# STM32_PAP_board.net
KiCad netlist of a schematic drawn in EAGLE
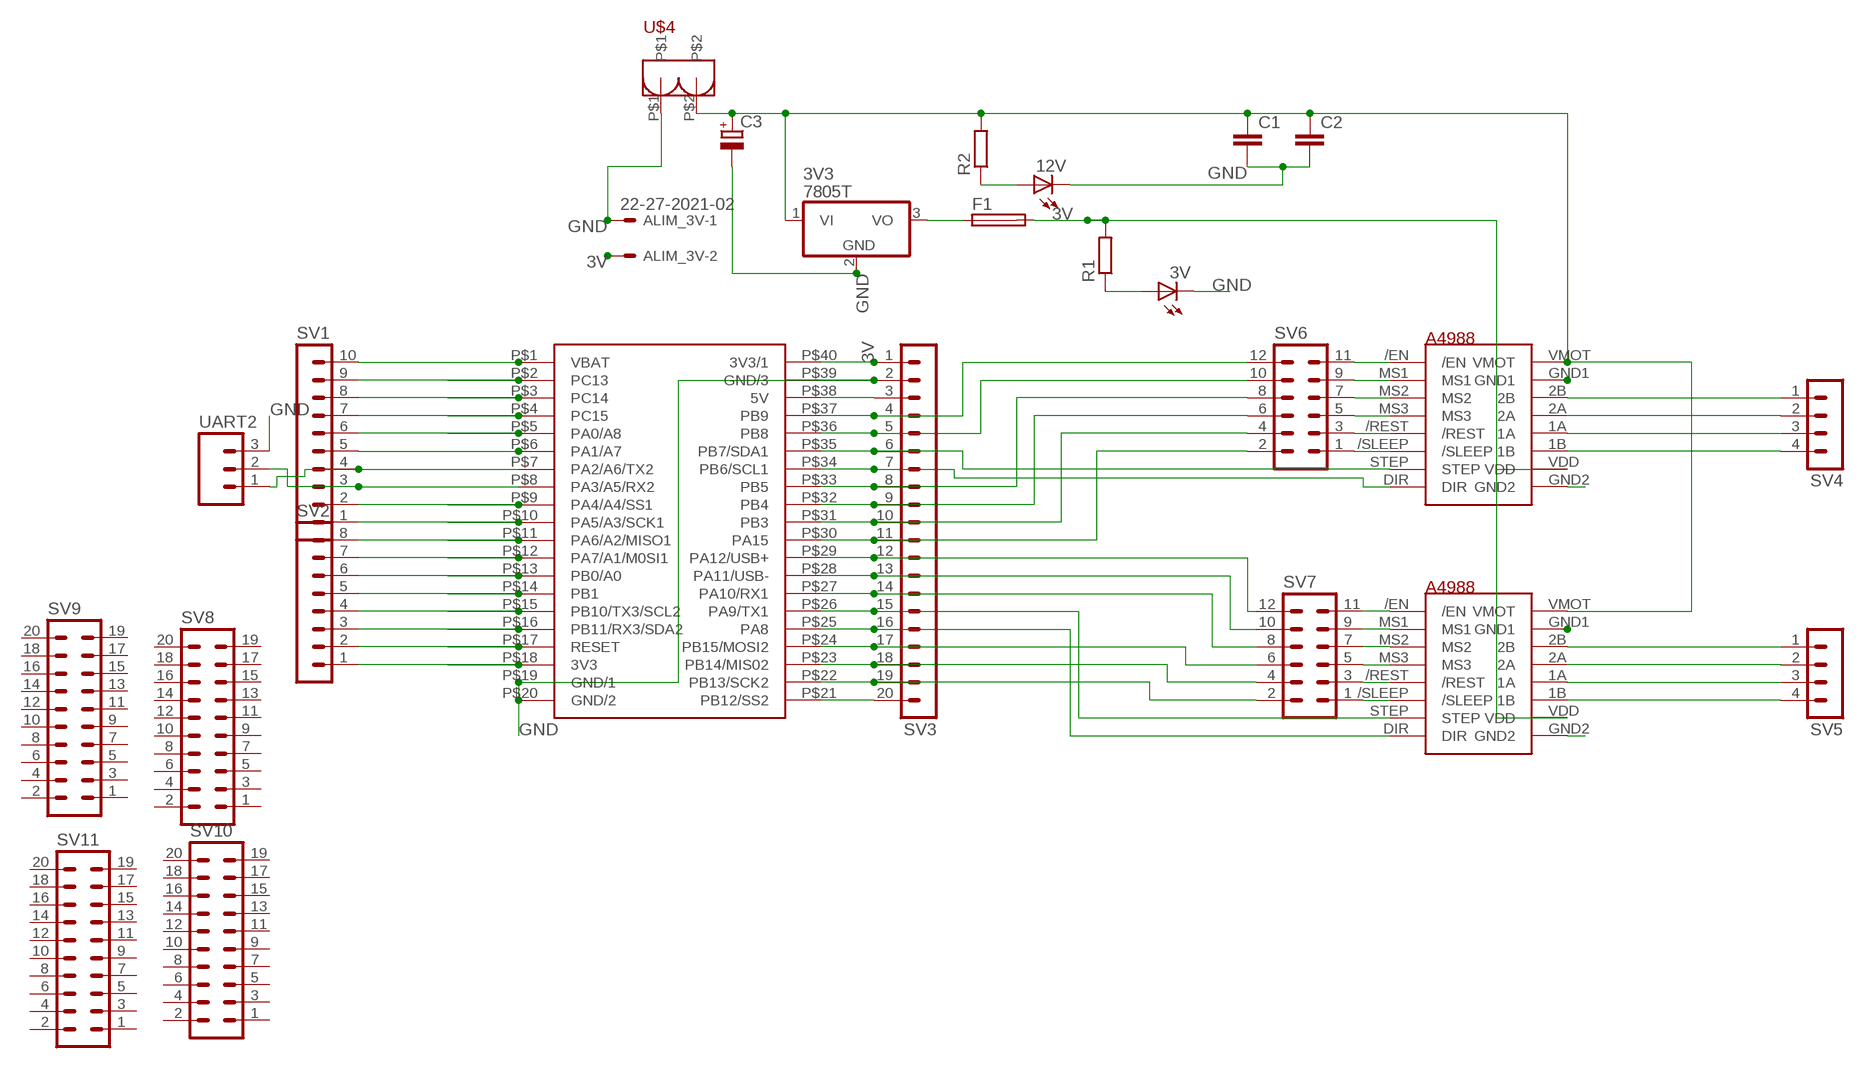
[diagram p0: schematic, sheet 1]

(export (version "E")
  (design (tool "Eeschema 10.0.6"))
  (components
    (comp (ref "3V")
      (value "LED_ELD260")
      (footprint "eagle-import:LED_LD260")
      (libsource (lib "eagle-import") (part "LED_ELD260"))
    )
    (comp (ref "3V3")
      (value "7805T")
      (footprint "eagle-import:TO220H")
      (libsource (lib "eagle-import") (part "78T05"))
    )
    (comp (ref "12V")
      (value "LED_ELD260")
      (footprint "eagle-import:LED_LD260")
      (libsource (lib "eagle-import") (part "LED_ELD260"))
    )
    (comp (ref "ALIM_3V")
      (value "22-27-2021-02")
      (footprint "eagle-import:6410-02")
      (libsource (lib "eagle-import") (part "22-?-0227-2021"))
    )
    (comp (ref "C1")
      (value "C5/5")
      (footprint "eagle-import:C5B5")
      (libsource (lib "eagle-import") (part "C5/5"))
    )
    (comp (ref "C2")
      (value "C5/5")
      (footprint "eagle-import:C5B5")
      (libsource (lib "eagle-import") (part "C5/5"))
    )
    (comp (ref "C3")
      (value "CPOL-EUE5-13")
      (footprint "eagle-import:E5-13")
      (libsource (lib "eagle-import") (part "CPOL-EUE5-13"))
    )
    (comp (ref "F1")
      (value "TR5")
      (footprint "eagle-import:TR5")
      (libsource (lib "eagle-import") (part "TR5"))
    )
    (comp (ref "R1")
      (value "R0204/7")
      (footprint "eagle-import:0204_7")
      (libsource (lib "eagle-import") (part "R0204/7"))
    )
    (comp (ref "R2")
      (value "R0204/7")
      (footprint "eagle-import:0204_7")
      (libsource (lib "eagle-import") (part "R0204/7"))
    )
    (comp (ref "SV1")
      (value "MA10-1")
      (footprint "eagle-import:MA10-1")
      (libsource (lib "eagle-import") (part "MA10-1"))
    )
    (comp (ref "SV2")
      (value "MA08-1")
      (footprint "eagle-import:MA08-1")
      (libsource (lib "eagle-import") (part "MA08-1"))
    )
    (comp (ref "SV3")
      (value "MA20-1")
      (footprint "eagle-import:MA20-1")
      (libsource (lib "eagle-import") (part "MA20-1"))
    )
    (comp (ref "SV4")
      (value "MA04-1")
      (footprint "eagle-import:MA04-1")
      (libsource (lib "eagle-import") (part "MA04-1"))
    )
    (comp (ref "SV5")
      (value "MA04-1")
      (footprint "eagle-import:MA04-1")
      (libsource (lib "eagle-import") (part "MA04-1"))
    )
    (comp (ref "SV6")
      (value "MA06-2")
      (footprint "eagle-import:MA06-2")
      (libsource (lib "eagle-import") (part "MA06-2"))
    )
    (comp (ref "SV7")
      (value "MA06-2")
      (footprint "eagle-import:MA06-2")
      (libsource (lib "eagle-import") (part "MA06-2"))
    )
    (comp (ref "SV8")
      (value "MA10-2")
      (footprint "eagle-import:MA10-2")
      (libsource (lib "eagle-import") (part "MA10-2"))
    )
    (comp (ref "SV9")
      (value "MA10-2")
      (footprint "eagle-import:MA10-2")
      (libsource (lib "eagle-import") (part "MA10-2"))
    )
    (comp (ref "SV10")
      (value "MA10-2")
      (footprint "eagle-import:MA10-2")
      (libsource (lib "eagle-import") (part "MA10-2"))
    )
    (comp (ref "SV11")
      (value "MA10-2")
      (footprint "eagle-import:MA10-2")
      (libsource (lib "eagle-import") (part "MA10-2"))
    )
    (comp (ref "U$1")
      (value "POLOLU_A4988_MOTOR_DRIVER")
      (footprint "eagle-import:POLOLU_A4988_MOTOR_DRIVER")
      (libsource (lib "eagle-import") (part "POLOLU_A4988_MOTOR_DRIVER"))
    )
    (comp (ref "U$2")
      (value "POLOLU_A4988_MOTOR_DRIVER")
      (footprint "eagle-import:POLOLU_A4988_MOTOR_DRIVER")
      (libsource (lib "eagle-import") (part "POLOLU_A4988_MOTOR_DRIVER"))
    )
    (comp (ref "U$3")
      (value "BLUEPILL")
      (footprint "eagle-import:BLUEPILL")
      (libsource (lib "eagle-import") (part "BLUEPILL"))
    )
    (comp (ref "U$4")
      (value "GREEN_HEADER")
      (footprint "eagle-import:GREEN_HEADER")
      (libsource (lib "eagle-import") (part "GREEN_HEADER"))
    )
    (comp (ref "UART2")
      (value "MA03")
      (footprint "eagle-import:03P")
      (libsource (lib "eagle-import") (part "MA03"))
    )
  )
  (nets
    (net (code "1") (name "/3V") (class "Default")
      (node (ref "ALIM_3V") (pin "2") (pinfunction "S_2") (pintype "passive"))
      (node (ref "F1") (pin "2") (pinfunction "2_2") (pintype "passive"))
      (node (ref "R1") (pin "2") (pinfunction "2_2") (pintype "passive"))
      (node (ref "SV3") (pin "1") (pinfunction "1_1") (pintype "passive"))
      (node (ref "U$1") (pin "VDD") (pinfunction "VDD_VDD") (pintype "bidirectional"))
      (node (ref "U$2") (pin "VDD") (pinfunction "VDD_VDD") (pintype "bidirectional"))
      (node (ref "U$3") (pin "P$40") (pinfunction "3V3/1_P$40") (pintype "bidirectional"))
    )
    (net (code "2") (name "/GND") (class "Default")
      (node (ref "12V") (pin "K") (pinfunction "C_K") (pintype "passive"))
      (node (ref "3V") (pin "K") (pinfunction "C_K") (pintype "passive"))
      (node (ref "3V3") (pin "2") (pinfunction "GND_2") (pintype "passive"))
      (node (ref "ALIM_3V") (pin "1") (pinfunction "S_1") (pintype "passive"))
      (node (ref "C1") (pin "2") (pinfunction "2_2") (pintype "passive"))
      (node (ref "C2") (pin "2") (pinfunction "2_2") (pintype "passive"))
      (node (ref "C3") (pin "-") (pinfunction "-_-") (pintype "passive"))
      (node (ref "SV3") (pin "2") (pinfunction "2_2") (pintype "passive"))
      (node (ref "U$3") (pin "P$19") (pinfunction "GND/1_P$19") (pintype "bidirectional"))
      (node (ref "U$3") (pin "P$20") (pinfunction "GND/2_P$20") (pintype "bidirectional"))
      (node (ref "U$3") (pin "P$39") (pinfunction "GND/3_P$39") (pintype "bidirectional"))
      (node (ref "U$4") (pin "P$1") (pinfunction "P$1_P$1") (pintype "bidirectional"))
      (node (ref "UART2") (pin "3") (pinfunction "3_3") (pintype "passive"))
    )
    (net (code "3") (name "Net-(3V-PadA)") (class "Default")
      (node (ref "3V") (pin "A") (pinfunction "A_A") (pintype "passive"))
      (node (ref "R1") (pin "1") (pinfunction "1_1") (pintype "passive"))
    )
    (net (code "4") (name "Net-(3V3-VI)") (class "Default")
      (node (ref "3V3") (pin "1") (pinfunction "VI_1") (pintype "input"))
      (node (ref "C1") (pin "1") (pinfunction "1_1") (pintype "passive"))
      (node (ref "C2") (pin "1") (pinfunction "1_1") (pintype "passive"))
      (node (ref "C3") (pin "+") (pinfunction "+_+") (pintype "passive"))
      (node (ref "R2") (pin "2") (pinfunction "2_2") (pintype "passive"))
      (node (ref "U$1") (pin "VMOT") (pinfunction "VMOT_VMOT") (pintype "bidirectional"))
      (node (ref "U$2") (pin "VMOT") (pinfunction "VMOT_VMOT") (pintype "bidirectional"))
      (node (ref "U$4") (pin "P$2") (pinfunction "P$2_P$2") (pintype "bidirectional"))
    )
    (net (code "5") (name "Net-(3V3-VO)") (class "Default")
      (node (ref "3V3") (pin "3") (pinfunction "VO_3") (pintype "passive"))
      (node (ref "F1") (pin "1") (pinfunction "1_1") (pintype "passive"))
    )
    (net (code "6") (name "Net-(12V-PadA)") (class "Default")
      (node (ref "12V") (pin "A") (pinfunction "A_A") (pintype "passive"))
      (node (ref "R2") (pin "1") (pinfunction "1_1") (pintype "passive"))
    )
    (net (code "7") (name "Net-(SV4-Pad1)") (class "Default")
      (node (ref "SV4") (pin "1") (pinfunction "1_1") (pintype "passive"))
      (node (ref "U$1") (pin "2B") (pinfunction "2B_2B") (pintype "bidirectional"))
    )
    (net (code "8") (name "Net-(SV4-Pad2)") (class "Default")
      (node (ref "SV4") (pin "2") (pinfunction "2_2") (pintype "passive"))
      (node (ref "U$1") (pin "2A") (pinfunction "2A_2A") (pintype "bidirectional"))
    )
    (net (code "9") (name "Net-(SV4-Pad3)") (class "Default")
      (node (ref "SV4") (pin "3") (pinfunction "3_3") (pintype "passive"))
      (node (ref "U$1") (pin "1A") (pinfunction "1A_1A") (pintype "bidirectional"))
    )
    (net (code "10") (name "Net-(SV4-Pad4)") (class "Default")
      (node (ref "SV4") (pin "4") (pinfunction "4_4") (pintype "passive"))
      (node (ref "U$1") (pin "1B") (pinfunction "1B_1B") (pintype "bidirectional"))
    )
    (net (code "11") (name "Net-(SV5-Pad1)") (class "Default")
      (node (ref "SV5") (pin "1") (pinfunction "1_1") (pintype "passive"))
      (node (ref "U$2") (pin "2B") (pinfunction "2B_2B") (pintype "bidirectional"))
    )
    (net (code "12") (name "Net-(SV5-Pad2)") (class "Default")
      (node (ref "SV5") (pin "2") (pinfunction "2_2") (pintype "passive"))
      (node (ref "U$2") (pin "2A") (pinfunction "2A_2A") (pintype "bidirectional"))
    )
    (net (code "13") (name "Net-(SV5-Pad3)") (class "Default")
      (node (ref "SV5") (pin "3") (pinfunction "3_3") (pintype "passive"))
      (node (ref "U$2") (pin "1A") (pinfunction "1A_1A") (pintype "bidirectional"))
    )
    (net (code "14") (name "Net-(SV5-Pad4)") (class "Default")
      (node (ref "SV5") (pin "4") (pinfunction "4_4") (pintype "passive"))
      (node (ref "U$2") (pin "1B") (pinfunction "1B_1B") (pintype "bidirectional"))
    )
    (net (code "15") (name "Net-(SV6-Pad1)") (class "Default")
      (node (ref "SV6") (pin "1") (pinfunction "1_1") (pintype "passive"))
      (node (ref "U$1") (pin "/SLEEP") (pinfunction "/SLEEP_/SLEEP") (pintype "bidirectional"))
    )
    (net (code "16") (name "Net-(SV6-Pad3)") (class "Default")
      (node (ref "SV6") (pin "3") (pinfunction "3_3") (pintype "passive"))
      (node (ref "U$1") (pin "/REST") (pinfunction "/REST_/REST") (pintype "bidirectional"))
    )
    (net (code "17") (name "Net-(SV6-Pad5)") (class "Default")
      (node (ref "SV6") (pin "5") (pinfunction "5_5") (pintype "passive"))
      (node (ref "U$1") (pin "MS3") (pinfunction "MS3_MS3") (pintype "bidirectional"))
    )
    (net (code "18") (name "Net-(SV6-Pad7)") (class "Default")
      (node (ref "SV6") (pin "7") (pinfunction "7_7") (pintype "passive"))
      (node (ref "U$1") (pin "MS2") (pinfunction "MS2_MS2") (pintype "bidirectional"))
    )
    (net (code "19") (name "Net-(SV6-Pad9)") (class "Default")
      (node (ref "SV6") (pin "9") (pinfunction "9_9") (pintype "passive"))
      (node (ref "U$1") (pin "MS1") (pinfunction "MS1_MS1") (pintype "bidirectional"))
    )
    (net (code "20") (name "Net-(SV6-Pad11)") (class "Default")
      (node (ref "SV6") (pin "11") (pinfunction "11_11") (pintype "passive"))
      (node (ref "U$1") (pin "/EN") (pinfunction "/EN_/EN") (pintype "bidirectional"))
    )
    (net (code "21") (name "Net-(SV7-Pad1)") (class "Default")
      (node (ref "SV7") (pin "1") (pinfunction "1_1") (pintype "passive"))
      (node (ref "U$2") (pin "/SLEEP") (pinfunction "/SLEEP_/SLEEP") (pintype "bidirectional"))
    )
    (net (code "22") (name "Net-(SV7-Pad3)") (class "Default")
      (node (ref "SV7") (pin "3") (pinfunction "3_3") (pintype "passive"))
      (node (ref "U$2") (pin "/REST") (pinfunction "/REST_/REST") (pintype "bidirectional"))
    )
    (net (code "23") (name "Net-(SV7-Pad5)") (class "Default")
      (node (ref "SV7") (pin "5") (pinfunction "5_5") (pintype "passive"))
      (node (ref "U$2") (pin "MS3") (pinfunction "MS3_MS3") (pintype "bidirectional"))
    )
    (net (code "24") (name "Net-(SV7-Pad7)") (class "Default")
      (node (ref "SV7") (pin "7") (pinfunction "7_7") (pintype "passive"))
      (node (ref "U$2") (pin "MS2") (pinfunction "MS2_MS2") (pintype "bidirectional"))
    )
    (net (code "25") (name "Net-(SV7-Pad9)") (class "Default")
      (node (ref "SV7") (pin "9") (pinfunction "9_9") (pintype "passive"))
      (node (ref "U$2") (pin "MS1") (pinfunction "MS1_MS1") (pintype "bidirectional"))
    )
    (net (code "26") (name "Net-(SV7-Pad11)") (class "Default")
      (node (ref "SV7") (pin "11") (pinfunction "11_11") (pintype "passive"))
      (node (ref "U$2") (pin "/EN") (pinfunction "/EN_/EN") (pintype "bidirectional"))
    )
    (net (code "27") (name "Net-(U$3-3V3)") (class "Default")
      (node (ref "SV2") (pin "1") (pinfunction "1_1") (pintype "passive"))
      (node (ref "U$3") (pin "P$18") (pinfunction "3V3_P$18") (pintype "bidirectional"))
    )
    (net (code "28") (name "Net-(U$3-5V)") (class "Default")
      (node (ref "SV3") (pin "3") (pinfunction "3_3") (pintype "passive"))
      (node (ref "U$3") (pin "P$38") (pinfunction "5V_P$38") (pintype "bidirectional"))
    )
    (net (code "29") (name "Net-(U$3-PA0{slash}A8)") (class "Default")
      (node (ref "SV1") (pin "6") (pinfunction "6_6") (pintype "passive"))
      (node (ref "U$3") (pin "P$5") (pinfunction "PA0/A8_P$5") (pintype "bidirectional"))
    )
    (net (code "30") (name "Net-(U$3-PA1{slash}A7)") (class "Default")
      (node (ref "SV1") (pin "5") (pinfunction "5_5") (pintype "passive"))
      (node (ref "U$3") (pin "P$6") (pinfunction "PA1/A7_P$6") (pintype "bidirectional"))
    )
    (net (code "31") (name "Net-(U$3-PA2{slash}A6{slash}TX2)") (class "Default")
      (node (ref "SV1") (pin "4") (pinfunction "4_4") (pintype "passive"))
      (node (ref "U$3") (pin "P$7") (pinfunction "PA2/A6/TX2_P$7") (pintype "bidirectional"))
      (node (ref "UART2") (pin "1") (pinfunction "1_1") (pintype "passive"))
    )
    (net (code "32") (name "Net-(U$3-PA3{slash}A5{slash}RX2)") (class "Default")
      (node (ref "SV1") (pin "3") (pinfunction "3_3") (pintype "passive"))
      (node (ref "U$3") (pin "P$8") (pinfunction "PA3/A5/RX2_P$8") (pintype "bidirectional"))
      (node (ref "UART2") (pin "2") (pinfunction "2_2") (pintype "passive"))
    )
    (net (code "33") (name "Net-(U$3-PA4{slash}A4{slash}SS1)") (class "Default")
      (node (ref "SV1") (pin "2") (pinfunction "2_2") (pintype "passive"))
      (node (ref "U$3") (pin "P$9") (pinfunction "PA4/A4/SS1_P$9") (pintype "bidirectional"))
    )
    (net (code "34") (name "Net-(U$3-PA5{slash}A3{slash}SCK1)") (class "Default")
      (node (ref "SV1") (pin "1") (pinfunction "1_1") (pintype "passive"))
      (node (ref "U$3") (pin "P$10") (pinfunction "PA5/A3/SCK1_P$10") (pintype "bidirectional"))
    )
    (net (code "35") (name "Net-(U$3-PA6{slash}A2{slash}MISO1)") (class "Default")
      (node (ref "SV2") (pin "8") (pinfunction "8_8") (pintype "passive"))
      (node (ref "U$3") (pin "P$11") (pinfunction "PA6/A2/MISO1_P$11") (pintype "bidirectional"))
    )
    (net (code "36") (name "Net-(U$3-PA7{slash}A1{slash}M0SI1)") (class "Default")
      (node (ref "SV2") (pin "7") (pinfunction "7_7") (pintype "passive"))
      (node (ref "U$3") (pin "P$12") (pinfunction "PA7/A1/M0SI1_P$12") (pintype "bidirectional"))
    )
    (net (code "37") (name "Net-(U$3-PA8)") (class "Default")
      (node (ref "SV3") (pin "16") (pinfunction "16_16") (pintype "passive"))
      (node (ref "U$2") (pin "DIR") (pinfunction "DIR_DIR") (pintype "bidirectional"))
      (node (ref "U$3") (pin "P$25") (pinfunction "PA8_P$25") (pintype "bidirectional"))
    )
    (net (code "38") (name "Net-(U$3-PA9{slash}TX1)") (class "Default")
      (node (ref "SV3") (pin "15") (pinfunction "15_15") (pintype "passive"))
      (node (ref "U$2") (pin "STEP") (pinfunction "STEP_STEP") (pintype "bidirectional"))
      (node (ref "U$3") (pin "P$26") (pinfunction "PA9/TX1_P$26") (pintype "bidirectional"))
    )
    (net (code "39") (name "Net-(U$3-PA10{slash}RX1)") (class "Default")
      (node (ref "SV3") (pin "14") (pinfunction "14_14") (pintype "passive"))
      (node (ref "SV7") (pin "8") (pinfunction "8_8") (pintype "passive"))
      (node (ref "U$3") (pin "P$27") (pinfunction "PA10/RX1_P$27") (pintype "bidirectional"))
    )
    (net (code "40") (name "Net-(U$3-PA11{slash}USB-)") (class "Default")
      (node (ref "SV3") (pin "13") (pinfunction "13_13") (pintype "passive"))
      (node (ref "SV7") (pin "10") (pinfunction "10_10") (pintype "passive"))
      (node (ref "U$3") (pin "P$28") (pinfunction "PA11/USB-_P$28") (pintype "bidirectional"))
    )
    (net (code "41") (name "Net-(U$3-PA12{slash}USB+)") (class "Default")
      (node (ref "SV3") (pin "12") (pinfunction "12_12") (pintype "passive"))
      (node (ref "SV7") (pin "12") (pinfunction "12_12") (pintype "passive"))
      (node (ref "U$3") (pin "P$29") (pinfunction "PA12/USB+_P$29") (pintype "bidirectional"))
    )
    (net (code "42") (name "Net-(U$3-PA15)") (class "Default")
      (node (ref "SV3") (pin "11") (pinfunction "11_11") (pintype "passive"))
      (node (ref "SV6") (pin "2") (pinfunction "2_2") (pintype "passive"))
      (node (ref "U$3") (pin "P$30") (pinfunction "PA15_P$30") (pintype "bidirectional"))
    )
    (net (code "43") (name "Net-(U$3-PB0{slash}A0)") (class "Default")
      (node (ref "SV2") (pin "6") (pinfunction "6_6") (pintype "passive"))
      (node (ref "U$3") (pin "P$13") (pinfunction "PB0/A0_P$13") (pintype "bidirectional"))
    )
    (net (code "44") (name "Net-(U$3-PB1)") (class "Default")
      (node (ref "SV2") (pin "5") (pinfunction "5_5") (pintype "passive"))
      (node (ref "U$3") (pin "P$14") (pinfunction "PB1_P$14") (pintype "bidirectional"))
    )
    (net (code "45") (name "Net-(U$3-PB3)") (class "Default")
      (node (ref "SV3") (pin "10") (pinfunction "10_10") (pintype "passive"))
      (node (ref "SV6") (pin "4") (pinfunction "4_4") (pintype "passive"))
      (node (ref "U$3") (pin "P$31") (pinfunction "PB3_P$31") (pintype "bidirectional"))
    )
    (net (code "46") (name "Net-(U$3-PB4)") (class "Default")
      (node (ref "SV3") (pin "9") (pinfunction "9_9") (pintype "passive"))
      (node (ref "SV6") (pin "6") (pinfunction "6_6") (pintype "passive"))
      (node (ref "U$3") (pin "P$32") (pinfunction "PB4_P$32") (pintype "bidirectional"))
    )
    (net (code "47") (name "Net-(U$3-PB5)") (class "Default")
      (node (ref "SV3") (pin "8") (pinfunction "8_8") (pintype "passive"))
      (node (ref "SV6") (pin "8") (pinfunction "8_8") (pintype "passive"))
      (node (ref "U$3") (pin "P$33") (pinfunction "PB5_P$33") (pintype "bidirectional"))
    )
    (net (code "48") (name "Net-(U$3-PB6{slash}SCL1)") (class "Default")
      (node (ref "SV3") (pin "7") (pinfunction "7_7") (pintype "passive"))
      (node (ref "U$1") (pin "DIR") (pinfunction "DIR_DIR") (pintype "bidirectional"))
      (node (ref "U$3") (pin "P$34") (pinfunction "PB6/SCL1_P$34") (pintype "bidirectional"))
    )
    (net (code "49") (name "Net-(U$3-PB7{slash}SDA1)") (class "Default")
      (node (ref "SV3") (pin "6") (pinfunction "6_6") (pintype "passive"))
      (node (ref "U$1") (pin "STEP") (pinfunction "STEP_STEP") (pintype "bidirectional"))
      (node (ref "U$3") (pin "P$35") (pinfunction "PB7/SDA1_P$35") (pintype "bidirectional"))
    )
    (net (code "50") (name "Net-(U$3-PB8)") (class "Default")
      (node (ref "SV3") (pin "5") (pinfunction "5_5") (pintype "passive"))
      (node (ref "SV6") (pin "10") (pinfunction "10_10") (pintype "passive"))
      (node (ref "U$3") (pin "P$36") (pinfunction "PB8_P$36") (pintype "bidirectional"))
    )
    (net (code "51") (name "Net-(U$3-PB9)") (class "Default")
      (node (ref "SV3") (pin "4") (pinfunction "4_4") (pintype "passive"))
      (node (ref "SV6") (pin "12") (pinfunction "12_12") (pintype "passive"))
      (node (ref "U$3") (pin "P$37") (pinfunction "PB9_P$37") (pintype "bidirectional"))
    )
    (net (code "52") (name "Net-(U$3-PB10{slash}TX3{slash}SCL2)") (class "Default")
      (node (ref "SV2") (pin "4") (pinfunction "4_4") (pintype "passive"))
      (node (ref "U$3") (pin "P$15") (pinfunction "PB10/TX3/SCL2_P$15") (pintype "bidirectional"))
    )
    (net (code "53") (name "Net-(U$3-PB11{slash}RX3{slash}SDA2)") (class "Default")
      (node (ref "SV2") (pin "3") (pinfunction "3_3") (pintype "passive"))
      (node (ref "U$3") (pin "P$16") (pinfunction "PB11/RX3/SDA2_P$16") (pintype "bidirectional"))
    )
    (net (code "54") (name "Net-(U$3-PB12{slash}SS2)") (class "Default")
      (node (ref "SV3") (pin "20") (pinfunction "20_20") (pintype "passive"))
      (node (ref "U$3") (pin "P$21") (pinfunction "PB12/SS2_P$21") (pintype "bidirectional"))
    )
    (net (code "55") (name "Net-(U$3-PB13{slash}SCK2)") (class "Default")
      (node (ref "SV3") (pin "19") (pinfunction "19_19") (pintype "passive"))
      (node (ref "SV7") (pin "2") (pinfunction "2_2") (pintype "passive"))
      (node (ref "U$3") (pin "P$22") (pinfunction "PB13/SCK2_P$22") (pintype "bidirectional"))
    )
    (net (code "56") (name "Net-(U$3-PB14{slash}MIS02)") (class "Default")
      (node (ref "SV3") (pin "18") (pinfunction "18_18") (pintype "passive"))
      (node (ref "SV7") (pin "4") (pinfunction "4_4") (pintype "passive"))
      (node (ref "U$3") (pin "P$23") (pinfunction "PB14/MIS02_P$23") (pintype "bidirectional"))
    )
    (net (code "57") (name "Net-(U$3-PB15{slash}MOSI2)") (class "Default")
      (node (ref "SV3") (pin "17") (pinfunction "17_17") (pintype "passive"))
      (node (ref "SV7") (pin "6") (pinfunction "6_6") (pintype "passive"))
      (node (ref "U$3") (pin "P$24") (pinfunction "PB15/MOSI2_P$24") (pintype "bidirectional"))
    )
    (net (code "58") (name "Net-(U$3-PC13)") (class "Default")
      (node (ref "SV1") (pin "9") (pinfunction "9_9") (pintype "passive"))
      (node (ref "U$3") (pin "P$2") (pinfunction "PC13_P$2") (pintype "bidirectional"))
    )
    (net (code "59") (name "Net-(U$3-PC14)") (class "Default")
      (node (ref "SV1") (pin "8") (pinfunction "8_8") (pintype "passive"))
      (node (ref "U$3") (pin "P$3") (pinfunction "PC14_P$3") (pintype "bidirectional"))
    )
    (net (code "60") (name "Net-(U$3-PC15)") (class "Default")
      (node (ref "SV1") (pin "7") (pinfunction "7_7") (pintype "passive"))
      (node (ref "U$3") (pin "P$4") (pinfunction "PC15_P$4") (pintype "bidirectional"))
    )
    (net (code "61") (name "Net-(U$3-RESET)") (class "Default")
      (node (ref "SV2") (pin "2") (pinfunction "2_2") (pintype "passive"))
      (node (ref "U$3") (pin "P$17") (pinfunction "RESET_P$17") (pintype "bidirectional"))
    )
    (net (code "62") (name "Net-(U$3-VBAT)") (class "Default")
      (node (ref "SV1") (pin "10") (pinfunction "10_10") (pintype "passive"))
      (node (ref "U$3") (pin "P$1") (pinfunction "VBAT_P$1") (pintype "bidirectional"))
    )
    (net (code "63") (name "unconnected-(SV8-Pad1)") (class "Default")
      (node (ref "SV8") (pin "1") (pinfunction "1_1") (pintype "passive"))
    )
    (net (code "64") (name "unconnected-(SV8-Pad2)") (class "Default")
      (node (ref "SV8") (pin "2") (pinfunction "2_2") (pintype "passive"))
    )
    (net (code "65") (name "unconnected-(SV8-Pad3)") (class "Default")
      (node (ref "SV8") (pin "3") (pinfunction "3_3") (pintype "passive"))
    )
    (net (code "66") (name "unconnected-(SV8-Pad4)") (class "Default")
      (node (ref "SV8") (pin "4") (pinfunction "4_4") (pintype "passive"))
    )
    (net (code "67") (name "unconnected-(SV8-Pad5)") (class "Default")
      (node (ref "SV8") (pin "5") (pinfunction "5_5") (pintype "passive"))
    )
    (net (code "68") (name "unconnected-(SV8-Pad6)") (class "Default")
      (node (ref "SV8") (pin "6") (pinfunction "6_6") (pintype "passive"))
    )
    (net (code "69") (name "unconnected-(SV8-Pad7)") (class "Default")
      (node (ref "SV8") (pin "7") (pinfunction "7_7") (pintype "passive"))
    )
    (net (code "70") (name "unconnected-(SV8-Pad8)") (class "Default")
      (node (ref "SV8") (pin "8") (pinfunction "8_8") (pintype "passive"))
    )
    (net (code "71") (name "unconnected-(SV8-Pad9)") (class "Default")
      (node (ref "SV8") (pin "9") (pinfunction "9_9") (pintype "passive"))
    )
    (net (code "72") (name "unconnected-(SV8-Pad10)") (class "Default")
      (node (ref "SV8") (pin "10") (pinfunction "10_10") (pintype "passive"))
    )
    (net (code "73") (name "unconnected-(SV8-Pad11)") (class "Default")
      (node (ref "SV8") (pin "11") (pinfunction "11_11") (pintype "passive"))
    )
    (net (code "74") (name "unconnected-(SV8-Pad12)") (class "Default")
      (node (ref "SV8") (pin "12") (pinfunction "12_12") (pintype "passive"))
    )
    (net (code "75") (name "unconnected-(SV8-Pad13)") (class "Default")
      (node (ref "SV8") (pin "13") (pinfunction "13_13") (pintype "passive"))
    )
    (net (code "76") (name "unconnected-(SV8-Pad14)") (class "Default")
      (node (ref "SV8") (pin "14") (pinfunction "14_14") (pintype "passive"))
    )
    (net (code "77") (name "unconnected-(SV8-Pad15)") (class "Default")
      (node (ref "SV8") (pin "15") (pinfunction "15_15") (pintype "passive"))
    )
    (net (code "78") (name "unconnected-(SV8-Pad16)") (class "Default")
      (node (ref "SV8") (pin "16") (pinfunction "16_16") (pintype "passive"))
    )
    (net (code "79") (name "unconnected-(SV8-Pad17)") (class "Default")
      (node (ref "SV8") (pin "17") (pinfunction "17_17") (pintype "passive"))
    )
    (net (code "80") (name "unconnected-(SV8-Pad18)") (class "Default")
      (node (ref "SV8") (pin "18") (pinfunction "18_18") (pintype "passive"))
    )
    (net (code "81") (name "unconnected-(SV8-Pad19)") (class "Default")
      (node (ref "SV8") (pin "19") (pinfunction "19_19") (pintype "passive"))
    )
    (net (code "82") (name "unconnected-(SV8-Pad20)") (class "Default")
      (node (ref "SV8") (pin "20") (pinfunction "20_20") (pintype "passive"))
    )
    (net (code "83") (name "unconnected-(SV9-Pad1)") (class "Default")
      (node (ref "SV9") (pin "1") (pinfunction "1_1") (pintype "passive"))
    )
    (net (code "84") (name "unconnected-(SV9-Pad2)") (class "Default")
      (node (ref "SV9") (pin "2") (pinfunction "2_2") (pintype "passive"))
    )
    (net (code "85") (name "unconnected-(SV9-Pad3)") (class "Default")
      (node (ref "SV9") (pin "3") (pinfunction "3_3") (pintype "passive"))
    )
    (net (code "86") (name "unconnected-(SV9-Pad4)") (class "Default")
      (node (ref "SV9") (pin "4") (pinfunction "4_4") (pintype "passive"))
    )
    (net (code "87") (name "unconnected-(SV9-Pad5)") (class "Default")
      (node (ref "SV9") (pin "5") (pinfunction "5_5") (pintype "passive"))
    )
    (net (code "88") (name "unconnected-(SV9-Pad6)") (class "Default")
      (node (ref "SV9") (pin "6") (pinfunction "6_6") (pintype "passive"))
    )
    (net (code "89") (name "unconnected-(SV9-Pad7)") (class "Default")
      (node (ref "SV9") (pin "7") (pinfunction "7_7") (pintype "passive"))
    )
    (net (code "90") (name "unconnected-(SV9-Pad8)") (class "Default")
      (node (ref "SV9") (pin "8") (pinfunction "8_8") (pintype "passive"))
    )
    (net (code "91") (name "unconnected-(SV9-Pad9)") (class "Default")
      (node (ref "SV9") (pin "9") (pinfunction "9_9") (pintype "passive"))
    )
    (net (code "92") (name "unconnected-(SV9-Pad10)") (class "Default")
      (node (ref "SV9") (pin "10") (pinfunction "10_10") (pintype "passive"))
    )
    (net (code "93") (name "unconnected-(SV9-Pad11)") (class "Default")
      (node (ref "SV9") (pin "11") (pinfunction "11_11") (pintype "passive"))
    )
    (net (code "94") (name "unconnected-(SV9-Pad12)") (class "Default")
      (node (ref "SV9") (pin "12") (pinfunction "12_12") (pintype "passive"))
    )
    (net (code "95") (name "unconnected-(SV9-Pad13)") (class "Default")
      (node (ref "SV9") (pin "13") (pinfunction "13_13") (pintype "passive"))
    )
    (net (code "96") (name "unconnected-(SV9-Pad14)") (class "Default")
      (node (ref "SV9") (pin "14") (pinfunction "14_14") (pintype "passive"))
    )
    (net (code "97") (name "unconnected-(SV9-Pad15)") (class "Default")
      (node (ref "SV9") (pin "15") (pinfunction "15_15") (pintype "passive"))
    )
    (net (code "98") (name "unconnected-(SV9-Pad16)") (class "Default")
      (node (ref "SV9") (pin "16") (pinfunction "16_16") (pintype "passive"))
    )
    (net (code "99") (name "unconnected-(SV9-Pad17)") (class "Default")
      (node (ref "SV9") (pin "17") (pinfunction "17_17") (pintype "passive"))
    )
    (net (code "100") (name "unconnected-(SV9-Pad18)") (class "Default")
      (node (ref "SV9") (pin "18") (pinfunction "18_18") (pintype "passive"))
    )
    (net (code "101") (name "unconnected-(SV9-Pad19)") (class "Default")
      (node (ref "SV9") (pin "19") (pinfunction "19_19") (pintype "passive"))
    )
    (net (code "102") (name "unconnected-(SV9-Pad20)") (class "Default")
      (node (ref "SV9") (pin "20") (pinfunction "20_20") (pintype "passive"))
    )
    (net (code "103") (name "unconnected-(SV10-Pad1)") (class "Default")
      (node (ref "SV10") (pin "1") (pinfunction "1_1") (pintype "passive"))
    )
    (net (code "104") (name "unconnected-(SV10-Pad2)") (class "Default")
      (node (ref "SV10") (pin "2") (pinfunction "2_2") (pintype "passive"))
    )
    (net (code "105") (name "unconnected-(SV10-Pad3)") (class "Default")
      (node (ref "SV10") (pin "3") (pinfunction "3_3") (pintype "passive"))
    )
    (net (code "106") (name "unconnected-(SV10-Pad4)") (class "Default")
      (node (ref "SV10") (pin "4") (pinfunction "4_4") (pintype "passive"))
    )
    (net (code "107") (name "unconnected-(SV10-Pad5)") (class "Default")
      (node (ref "SV10") (pin "5") (pinfunction "5_5") (pintype "passive"))
    )
    (net (code "108") (name "unconnected-(SV10-Pad6)") (class "Default")
      (node (ref "SV10") (pin "6") (pinfunction "6_6") (pintype "passive"))
    )
    (net (code "109") (name "unconnected-(SV10-Pad7)") (class "Default")
      (node (ref "SV10") (pin "7") (pinfunction "7_7") (pintype "passive"))
    )
    (net (code "110") (name "unconnected-(SV10-Pad8)") (class "Default")
      (node (ref "SV10") (pin "8") (pinfunction "8_8") (pintype "passive"))
    )
    (net (code "111") (name "unconnected-(SV10-Pad9)") (class "Default")
      (node (ref "SV10") (pin "9") (pinfunction "9_9") (pintype "passive"))
    )
    (net (code "112") (name "unconnected-(SV10-Pad10)") (class "Default")
      (node (ref "SV10") (pin "10") (pinfunction "10_10") (pintype "passive"))
    )
    (net (code "113") (name "unconnected-(SV10-Pad11)") (class "Default")
      (node (ref "SV10") (pin "11") (pinfunction "11_11") (pintype "passive"))
    )
    (net (code "114") (name "unconnected-(SV10-Pad12)") (class "Default")
      (node (ref "SV10") (pin "12") (pinfunction "12_12") (pintype "passive"))
    )
    (net (code "115") (name "unconnected-(SV10-Pad13)") (class "Default")
      (node (ref "SV10") (pin "13") (pinfunction "13_13") (pintype "passive"))
    )
    (net (code "116") (name "unconnected-(SV10-Pad14)") (class "Default")
      (node (ref "SV10") (pin "14") (pinfunction "14_14") (pintype "passive"))
    )
    (net (code "117") (name "unconnected-(SV10-Pad15)") (class "Default")
      (node (ref "SV10") (pin "15") (pinfunction "15_15") (pintype "passive"))
    )
    (net (code "118") (name "unconnected-(SV10-Pad16)") (class "Default")
      (node (ref "SV10") (pin "16") (pinfunction "16_16") (pintype "passive"))
    )
    (net (code "119") (name "unconnected-(SV10-Pad17)") (class "Default")
      (node (ref "SV10") (pin "17") (pinfunction "17_17") (pintype "passive"))
    )
    (net (code "120") (name "unconnected-(SV10-Pad18)") (class "Default")
      (node (ref "SV10") (pin "18") (pinfunction "18_18") (pintype "passive"))
    )
    (net (code "121") (name "unconnected-(SV10-Pad19)") (class "Default")
      (node (ref "SV10") (pin "19") (pinfunction "19_19") (pintype "passive"))
    )
    (net (code "122") (name "unconnected-(SV10-Pad20)") (class "Default")
      (node (ref "SV10") (pin "20") (pinfunction "20_20") (pintype "passive"))
    )
    (net (code "123") (name "unconnected-(SV11-Pad1)") (class "Default")
      (node (ref "SV11") (pin "1") (pinfunction "1_1") (pintype "passive"))
    )
    (net (code "124") (name "unconnected-(SV11-Pad2)") (class "Default")
      (node (ref "SV11") (pin "2") (pinfunction "2_2") (pintype "passive"))
    )
    (net (code "125") (name "unconnected-(SV11-Pad3)") (class "Default")
      (node (ref "SV11") (pin "3") (pinfunction "3_3") (pintype "passive"))
    )
    (net (code "126") (name "unconnected-(SV11-Pad4)") (class "Default")
      (node (ref "SV11") (pin "4") (pinfunction "4_4") (pintype "passive"))
    )
    (net (code "127") (name "unconnected-(SV11-Pad5)") (class "Default")
      (node (ref "SV11") (pin "5") (pinfunction "5_5") (pintype "passive"))
    )
    (net (code "128") (name "unconnected-(SV11-Pad6)") (class "Default")
      (node (ref "SV11") (pin "6") (pinfunction "6_6") (pintype "passive"))
    )
    (net (code "129") (name "unconnected-(SV11-Pad7)") (class "Default")
      (node (ref "SV11") (pin "7") (pinfunction "7_7") (pintype "passive"))
    )
    (net (code "130") (name "unconnected-(SV11-Pad8)") (class "Default")
      (node (ref "SV11") (pin "8") (pinfunction "8_8") (pintype "passive"))
    )
    (net (code "131") (name "unconnected-(SV11-Pad9)") (class "Default")
      (node (ref "SV11") (pin "9") (pinfunction "9_9") (pintype "passive"))
    )
    (net (code "132") (name "unconnected-(SV11-Pad10)") (class "Default")
      (node (ref "SV11") (pin "10") (pinfunction "10_10") (pintype "passive"))
    )
    (net (code "133") (name "unconnected-(SV11-Pad11)") (class "Default")
      (node (ref "SV11") (pin "11") (pinfunction "11_11") (pintype "passive"))
    )
    (net (code "134") (name "unconnected-(SV11-Pad12)") (class "Default")
      (node (ref "SV11") (pin "12") (pinfunction "12_12") (pintype "passive"))
    )
    (net (code "135") (name "unconnected-(SV11-Pad13)") (class "Default")
      (node (ref "SV11") (pin "13") (pinfunction "13_13") (pintype "passive"))
    )
    (net (code "136") (name "unconnected-(SV11-Pad14)") (class "Default")
      (node (ref "SV11") (pin "14") (pinfunction "14_14") (pintype "passive"))
    )
    (net (code "137") (name "unconnected-(SV11-Pad15)") (class "Default")
      (node (ref "SV11") (pin "15") (pinfunction "15_15") (pintype "passive"))
    )
    (net (code "138") (name "unconnected-(SV11-Pad16)") (class "Default")
      (node (ref "SV11") (pin "16") (pinfunction "16_16") (pintype "passive"))
    )
    (net (code "139") (name "unconnected-(SV11-Pad17)") (class "Default")
      (node (ref "SV11") (pin "17") (pinfunction "17_17") (pintype "passive"))
    )
    (net (code "140") (name "unconnected-(SV11-Pad18)") (class "Default")
      (node (ref "SV11") (pin "18") (pinfunction "18_18") (pintype "passive"))
    )
    (net (code "141") (name "unconnected-(SV11-Pad19)") (class "Default")
      (node (ref "SV11") (pin "19") (pinfunction "19_19") (pintype "passive"))
    )
    (net (code "142") (name "unconnected-(SV11-Pad20)") (class "Default")
      (node (ref "SV11") (pin "20") (pinfunction "20_20") (pintype "passive"))
    )
    (net (code "143") (name "unconnected-(U$1-PadGND1)") (class "Default")
      (node (ref "U$1") (pin "GND1") (pinfunction "GND1_GND1") (pintype "bidirectional"))
    )
    (net (code "144") (name "unconnected-(U$1-PadGND2)") (class "Default")
      (node (ref "U$1") (pin "GND2") (pinfunction "GND2_GND2") (pintype "bidirectional"))
    )
    (net (code "145") (name "unconnected-(U$2-PadGND1)") (class "Default")
      (node (ref "U$2") (pin "GND1") (pinfunction "GND1_GND1") (pintype "bidirectional"))
    )
    (net (code "146") (name "unconnected-(U$2-PadGND2)") (class "Default")
      (node (ref "U$2") (pin "GND2") (pinfunction "GND2_GND2") (pintype "bidirectional"))
    )
  )
)
